# QRE1113-2.net
KiCad netlist of a schematic drawn in Altium Designer
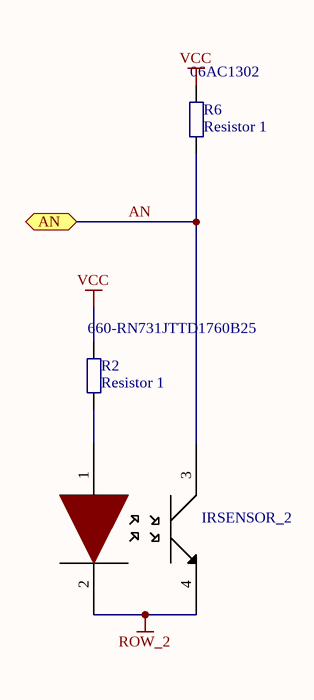
[diagram p0: QRE1113-2.SchDoc]

(export (version "E")
  (design (tool "Eeschema 10.0.6"))
  (components
    (comp (ref "IRSENSOR_2")
      (value "QRE1113GR")
      (footprint "QRE1113:QRE1113GR")
      (libsource (lib "Keyboard Library") (part "QRE1113GR"))
    )
    (comp (ref "R2")
      (value "Resistor 1")
      (footprint "R-0603")
      (description "Resistor")
      (fields (field (name "SUPPLIER PART NUMBER 1") "660-RN731JTTD1760B25"))
      (libsource (lib "Max Library") (part "Resistor 1"))
    )
    (comp (ref "R6")
      (value "Resistor 1")
      (footprint "R-0603")
      (description "Resistor")
      (fields (field (name "SUPPLIER PART NUMBER 1") "06AC1302"))
      (libsource (lib "") (part "Resistor 1_1"))
    )
  )
  (nets
    (net (code "1") (name "/AN") (class "Default")
      (node (ref "IRSENSOR_2") (pin "3") (pinfunction "3_3") (pintype "passive"))
      (node (ref "R6") (pin "2") (pinfunction "2_2") (pintype "passive"))
    )
    (net (code "2") (name "Net-(IRSENSOR_2-Pad1)") (class "Default")
      (node (ref "IRSENSOR_2") (pin "1") (pinfunction "1_1") (pintype "passive"))
      (node (ref "R2") (pin "1") (pinfunction "1_1") (pintype "passive"))
    )
    (net (code "3") (name "ROW_2") (class "Default")
      (node (ref "IRSENSOR_2") (pin "2") (pinfunction "2_2") (pintype "passive"))
      (node (ref "IRSENSOR_2") (pin "4") (pinfunction "4_4") (pintype "passive"))
    )
    (net (code "4") (name "VCC") (class "Default")
      (node (ref "R2") (pin "2") (pinfunction "2_2") (pintype "passive"))
      (node (ref "R6") (pin "1") (pinfunction "1_1") (pintype "passive"))
    )
  )
)
